# tuggerTrackerV1.net
KiCad netlist of a schematic drawn in EAGLE
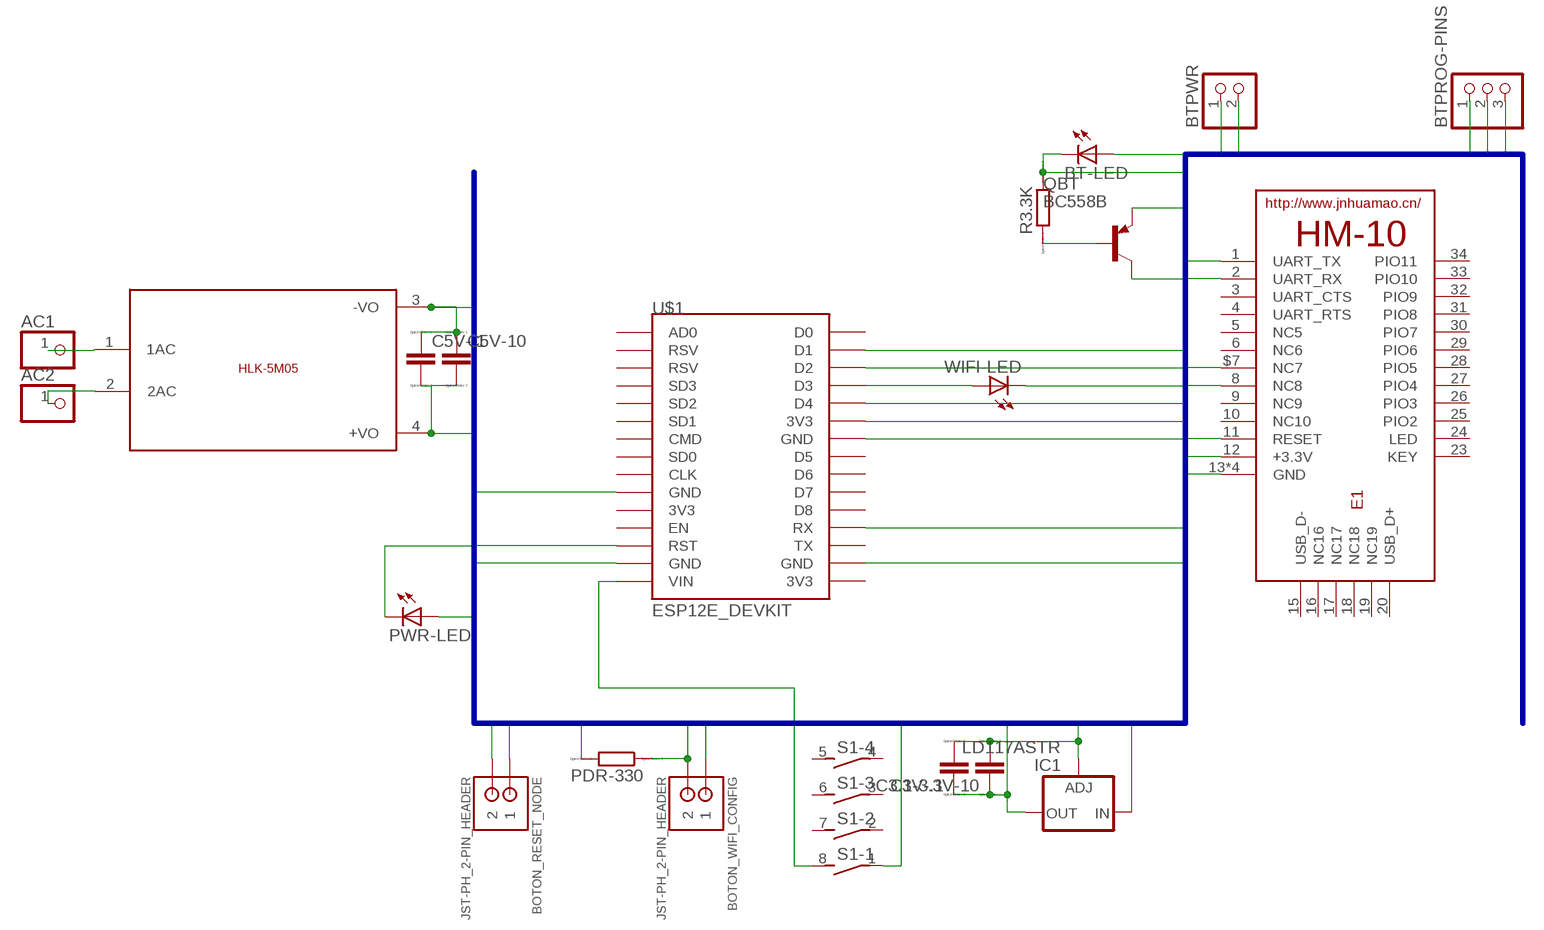
[diagram p0: schematic, sheet 1]

(export (version "E")
  (design (tool "Eeschema 10.0.6"))
  (components
    (comp (ref "AC1")
      (value "PINHD-1X1")
      (footprint "eagle-import:1X01")
      (libsource (lib "eagle-import") (part "PINHD-1X1"))
    )
    (comp (ref "AC2")
      (value "PINHD-1X1")
      (footprint "eagle-import:1X01")
      (libsource (lib "eagle-import") (part "PINHD-1X1"))
    )
    (comp (ref "BOTON_RESET_NODE")
      (value "JST-PH_2-PIN_HEADER")
      (footprint "eagle-import:JST_B2B-PH_HEADER")
      (libsource (lib "eagle-import") (part "JST-PH_2-PIN_HEADER"))
    )
    (comp (ref "BOTON_WIFI_CONFIG")
      (value "JST-PH_2-PIN_HEADER")
      (footprint "eagle-import:JST_B2B-PH_HEADER")
      (libsource (lib "eagle-import") (part "JST-PH_2-PIN_HEADER"))
    )
    (comp (ref "BT-LED")
      (value "LEDCHIPLED_1206")
      (footprint "eagle-import:CHIPLED_1206")
      (libsource (lib "eagle-import") (part "LEDCHIPLED_1206"))
    )
    (comp (ref "BTPROG-PINS")
      (value "PINHD-1X3")
      (footprint "eagle-import:1X03")
      (libsource (lib "eagle-import") (part "PINHD-1X3"))
    )
    (comp (ref "BTPWR")
      (value "PINHD-1X2")
      (footprint "eagle-import:1X02")
      (libsource (lib "eagle-import") (part "PINHD-1X2"))
    )
    (comp (ref "C1-3.3V-10")
      (value "CC0603")
      (footprint "eagle-import:C0603")
      (libsource (lib "eagle-import") (part "CC0603"))
    )
    (comp (ref "C3.3V-.1")
      (value "CC0603")
      (footprint "eagle-import:C0603")
      (libsource (lib "eagle-import") (part "CC0603"))
    )
    (comp (ref "C5V-.1")
      (value "CC0603")
      (footprint "eagle-import:C0603")
      (libsource (lib "eagle-import") (part "CC0603"))
    )
    (comp (ref "C5V-10")
      (value "CC0603")
      (footprint "eagle-import:C0603")
      (libsource (lib "eagle-import") (part "CC0603"))
    )
    (comp (ref "E1")
      (value "HM-10-BOARD")
      (footprint "eagle-import:26.9X13X2.2_BOARD")
      (libsource (lib "eagle-import") (part "HM-10-BOARD"))
    )
    (comp (ref "IC1")
      (value "LD117ASTR")
      (footprint "eagle-import:SOT223")
      (libsource (lib "eagle-import") (part "LD117A?STR"))
    )
    (comp (ref "PDR-330")
      (value "RR1206")
      (footprint "eagle-import:R1206")
      (libsource (lib "eagle-import") (part "RR1206"))
    )
    (comp (ref "PWR-LED")
      (value "LEDCHIPLED_1206")
      (footprint "eagle-import:CHIPLED_1206")
      (libsource (lib "eagle-import") (part "LEDCHIPLED_1206"))
    )
    (comp (ref "QBT")
      (value "BC558B")
      (footprint "eagle-import:TO92-EBC")
      (libsource (lib "eagle-import") (part "BC558B"))
    )
    (comp (ref "R3.3K")
      (value "RR1206")
      (footprint "eagle-import:R1206")
      (libsource (lib "eagle-import") (part "RR1206"))
    )
    (comp (ref "S1")
      (value "DIP04S")
      (footprint "eagle-import:DIP04S")
      (libsource (lib "eagle-import") (part "DIP04S"))
    )
    (comp (ref "U$1")
      (value "ESP12E_DEVKIT")
      (footprint "eagle-import:ESP12E_DEVKIT")
      (libsource (lib "eagle-import") (part "ESP12E_DEVKIT"))
    )
    (comp (ref "U$2")
      (value "5VDC/5W")
      (footprint "eagle-import:HLK-5M05")
      (libsource (lib "eagle-import") (part "HLK-5M05"))
    )
    (comp (ref "WIFI-LED")
      (value "LEDCHIPLED_1206")
      (footprint "eagle-import:CHIPLED_1206")
      (libsource (lib "eagle-import") (part "LEDCHIPLED_1206"))
    )
  )
  (nets
    (net (code "1") (name "/BTPG1") (class "Default")
      (node (ref "BTPROG-PINS") (pin "1") (pinfunction "1_1") (pintype "passive"))
      (node (ref "E1") (pin "$7") (pinfunction "NC7_$7") (pintype "bidirectional"))
    )
    (net (code "2") (name "/BTPG2") (class "Default")
      (node (ref "BTPROG-PINS") (pin "2") (pinfunction "2_2") (pintype "passive"))
      (node (ref "E1") (pin "8") (pinfunction "NC8_8") (pintype "bidirectional"))
    )
    (net (code "3") (name "/BTRST") (class "Default")
      (node (ref "BTPROG-PINS") (pin "3") (pinfunction "3_3") (pintype "passive"))
      (node (ref "E1") (pin "11") (pinfunction "RESET_11") (pintype "bidirectional"))
    )
    (net (code "4") (name "/BTVCC") (class "Default")
      (node (ref "E1") (pin "12") (pinfunction "+3.3V_12") (pintype "bidirectional"))
      (node (ref "QBT") (pin "C") (pinfunction "C_C") (pintype "passive"))
    )
    (net (code "5") (name "/D1") (class "Default")
      (node (ref "BT-LED") (pin "C") (pinfunction "C_C") (pintype "passive"))
      (node (ref "R3.3K") (pin "2") (pinfunction "2_2") (pintype "passive"))
      (node (ref "U$1") (pin "D1") (pinfunction "D1_D1") (pintype "bidirectional"))
    )
    (net (code "6") (name "/D2") (class "Default")
      (node (ref "BOTON_WIFI_CONFIG") (pin "P2") (pinfunction "2_P2") (pintype "bidirectional"))
      (node (ref "PDR-330") (pin "1") (pinfunction "1_1") (pintype "passive"))
      (node (ref "U$1") (pin "D2") (pinfunction "D2_D2") (pintype "bidirectional"))
    )
    (net (code "7") (name "/GND") (class "Default")
      (node (ref "BOTON_RESET_NODE") (pin "P2") (pinfunction "2_P2") (pintype "bidirectional"))
      (node (ref "BTPWR") (pin "1") (pinfunction "1_1") (pintype "passive"))
      (node (ref "C1-3.3V-10") (pin "2") (pinfunction "2_2") (pintype "passive"))
      (node (ref "C3.3V-.1") (pin "2") (pinfunction "2_2") (pintype "passive"))
      (node (ref "C5V-.1") (pin "1") (pinfunction "1_1") (pintype "passive"))
      (node (ref "C5V-10") (pin "1") (pinfunction "1_1") (pintype "passive"))
      (node (ref "E1") (pin "13") (pinfunction "GND_13") (pintype "bidirectional"))
      (node (ref "E1") (pin "14") (pinfunction "GND_14") (pintype "bidirectional"))
      (node (ref "E1") (pin "21") (pinfunction "GND_21") (pintype "bidirectional"))
      (node (ref "E1") (pin "22") (pinfunction "GND_22") (pintype "bidirectional"))
      (node (ref "IC1") (pin "1") (pinfunction "ADJ_1") (pintype "input"))
      (node (ref "PDR-330") (pin "2") (pinfunction "2_2") (pintype "passive"))
      (node (ref "PWR-LED") (pin "C") (pinfunction "C_C") (pintype "passive"))
      (node (ref "U$1") (pin "GND@0") (pinfunction "GND_GND@0") (pintype "bidirectional"))
      (node (ref "U$1") (pin "GND@1") (pinfunction "GND_GND@1") (pintype "bidirectional"))
      (node (ref "U$1") (pin "GND@2") (pinfunction "GND_GND@2") (pintype "bidirectional"))
      (node (ref "U$1") (pin "GND@3") (pinfunction "GND_GND@3") (pintype "bidirectional"))
      (node (ref "U$2") (pin "3") (pinfunction "-VO_3") (pintype "bidirectional"))
      (node (ref "WIFI-LED") (pin "C") (pinfunction "C_C") (pintype "passive"))
    )
    (net (code "8") (name "/NODRST") (class "Default")
      (node (ref "BOTON_RESET_NODE") (pin "P1") (pinfunction "1_P1") (pintype "bidirectional"))
      (node (ref "U$1") (pin "RST") (pinfunction "RST_RST") (pintype "bidirectional"))
    )
    (net (code "9") (name "/NRXBTX") (class "Default")
      (node (ref "E1") (pin "1") (pinfunction "UART_TX_1") (pintype "bidirectional"))
      (node (ref "U$1") (pin "RX") (pinfunction "RX_RX") (pintype "bidirectional"))
    )
    (net (code "10") (name "/NTXBRX") (class "Default")
      (node (ref "E1") (pin "2") (pinfunction "UART_RX_2") (pintype "bidirectional"))
      (node (ref "U$1") (pin "D4") (pinfunction "D4_D4") (pintype "bidirectional"))
    )
    (net (code "11") (name "/V3NODE") (class "Default")
      (node (ref "BOTON_WIFI_CONFIG") (pin "P1") (pinfunction "1_P1") (pintype "bidirectional"))
      (node (ref "BT-LED") (pin "A") (pinfunction "A_A") (pintype "passive"))
      (node (ref "PWR-LED") (pin "A") (pinfunction "A_A") (pintype "passive"))
      (node (ref "U$1") (pin "3V3@1") (pinfunction "3V3_3V3@1") (pintype "bidirectional"))
    )
    (net (code "12") (name "/V3REG") (class "Default")
      (node (ref "C1-3.3V-10") (pin "1") (pinfunction "1_1") (pintype "passive"))
      (node (ref "C3.3V-.1") (pin "1") (pinfunction "1_1") (pintype "passive"))
      (node (ref "IC1") (pin "4") (pinfunction "OUT_4") (pintype "passive"))
      (node (ref "QBT") (pin "E") (pinfunction "E_E") (pintype "passive"))
    )
    (net (code "13") (name "/VIN") (class "Default")
      (node (ref "BTPWR") (pin "2") (pinfunction "2_2") (pintype "passive"))
      (node (ref "C5V-.1") (pin "2") (pinfunction "2_2") (pintype "passive"))
      (node (ref "C5V-10") (pin "2") (pinfunction "2_2") (pintype "passive"))
      (node (ref "IC1") (pin "3") (pinfunction "IN_3") (pintype "input"))
      (node (ref "S1") (pin "1") (pinfunction "1_1") (pintype "passive"))
      (node (ref "U$2") (pin "4") (pinfunction "+VO_4") (pintype "bidirectional"))
    )
    (net (code "14") (name "Net-(QBT-PadB)") (class "Default")
      (node (ref "QBT") (pin "B") (pinfunction "B_B") (pintype "passive"))
      (node (ref "R3.3K") (pin "1") (pinfunction "1_1") (pintype "passive"))
    )
    (net (code "15") (name "Net-(S1A-2)") (class "Default")
      (node (ref "S1") (pin "8") (pinfunction "2_8") (pintype "passive"))
      (node (ref "U$1") (pin "VIN") (pinfunction "VIN_VIN") (pintype "bidirectional"))
    )
    (net (code "16") (name "Net-(U$1-PadD3)") (class "Default")
      (node (ref "U$1") (pin "D3") (pinfunction "D3_D3") (pintype "bidirectional"))
      (node (ref "WIFI-LED") (pin "A") (pinfunction "A_A") (pintype "passive"))
    )
    (net (code "17") (name "Net-(U$2-1AC)") (class "Default")
      (node (ref "AC1") (pin "1") (pinfunction "1_1") (pintype "passive"))
      (node (ref "U$2") (pin "1") (pinfunction "1AC_1") (pintype "bidirectional"))
    )
    (net (code "18") (name "Net-(U$2-2AC)") (class "Default")
      (node (ref "AC2") (pin "1") (pinfunction "1_1") (pintype "passive"))
      (node (ref "U$2") (pin "2") (pinfunction "2AC_2") (pintype "bidirectional"))
    )
    (net (code "19") (name "unconnected-(E1-KEY-Pad23)") (class "Default")
      (node (ref "E1") (pin "23") (pinfunction "KEY_23") (pintype "bidirectional"))
    )
    (net (code "20") (name "unconnected-(E1-LED-Pad24)") (class "Default")
      (node (ref "E1") (pin "24") (pinfunction "LED_24") (pintype "bidirectional"))
    )
    (net (code "21") (name "unconnected-(E1-NC5-Pad5)") (class "Default")
      (node (ref "E1") (pin "5") (pinfunction "NC5_5") (pintype "bidirectional"))
    )
    (net (code "22") (name "unconnected-(E1-NC6-Pad6)") (class "Default")
      (node (ref "E1") (pin "6") (pinfunction "NC6_6") (pintype "bidirectional"))
    )
    (net (code "23") (name "unconnected-(E1-NC9-Pad9)") (class "Default")
      (node (ref "E1") (pin "9") (pinfunction "NC9_9") (pintype "bidirectional"))
    )
    (net (code "24") (name "unconnected-(E1-NC10-Pad10)") (class "Default")
      (node (ref "E1") (pin "10") (pinfunction "NC10_10") (pintype "bidirectional"))
    )
    (net (code "25") (name "unconnected-(E1-NC16-Pad16)") (class "Default")
      (node (ref "E1") (pin "16") (pinfunction "NC16_16") (pintype "bidirectional"))
    )
    (net (code "26") (name "unconnected-(E1-NC17-Pad17)") (class "Default")
      (node (ref "E1") (pin "17") (pinfunction "NC17_17") (pintype "bidirectional"))
    )
    (net (code "27") (name "unconnected-(E1-NC18-Pad18)") (class "Default")
      (node (ref "E1") (pin "18") (pinfunction "NC18_18") (pintype "bidirectional"))
    )
    (net (code "28") (name "unconnected-(E1-NC19-Pad19)") (class "Default")
      (node (ref "E1") (pin "19") (pinfunction "NC19_19") (pintype "bidirectional"))
    )
    (net (code "29") (name "unconnected-(E1-PIO2-Pad25)") (class "Default")
      (node (ref "E1") (pin "25") (pinfunction "PIO2_25") (pintype "bidirectional"))
    )
    (net (code "30") (name "unconnected-(E1-PIO3-Pad26)") (class "Default")
      (node (ref "E1") (pin "26") (pinfunction "PIO3_26") (pintype "bidirectional"))
    )
    (net (code "31") (name "unconnected-(E1-PIO4-Pad27)") (class "Default")
      (node (ref "E1") (pin "27") (pinfunction "PIO4_27") (pintype "bidirectional"))
    )
    (net (code "32") (name "unconnected-(E1-PIO5-Pad28)") (class "Default")
      (node (ref "E1") (pin "28") (pinfunction "PIO5_28") (pintype "bidirectional"))
    )
    (net (code "33") (name "unconnected-(E1-PIO6-Pad29)") (class "Default")
      (node (ref "E1") (pin "29") (pinfunction "PIO6_29") (pintype "bidirectional"))
    )
    (net (code "34") (name "unconnected-(E1-PIO7-Pad30)") (class "Default")
      (node (ref "E1") (pin "30") (pinfunction "PIO7_30") (pintype "bidirectional"))
    )
    (net (code "35") (name "unconnected-(E1-PIO8-Pad31)") (class "Default")
      (node (ref "E1") (pin "31") (pinfunction "PIO8_31") (pintype "bidirectional"))
    )
    (net (code "36") (name "unconnected-(E1-PIO9-Pad32)") (class "Default")
      (node (ref "E1") (pin "32") (pinfunction "PIO9_32") (pintype "bidirectional"))
    )
    (net (code "37") (name "unconnected-(E1-PIO10-Pad33)") (class "Default")
      (node (ref "E1") (pin "33") (pinfunction "PIO10_33") (pintype "bidirectional"))
    )
    (net (code "38") (name "unconnected-(E1-PIO11-Pad34)") (class "Default")
      (node (ref "E1") (pin "34") (pinfunction "PIO11_34") (pintype "bidirectional"))
    )
    (net (code "39") (name "unconnected-(E1-UART_CTS-Pad3)") (class "Default")
      (node (ref "E1") (pin "3") (pinfunction "UART_CTS_3") (pintype "bidirectional"))
    )
    (net (code "40") (name "unconnected-(E1-UART_RTS-Pad4)") (class "Default")
      (node (ref "E1") (pin "4") (pinfunction "UART_RTS_4") (pintype "bidirectional"))
    )
    (net (code "41") (name "unconnected-(E1-USB_D+-Pad20)") (class "Default")
      (node (ref "E1") (pin "20") (pinfunction "USB_D+_20") (pintype "bidirectional"))
    )
    (net (code "42") (name "unconnected-(E1-USB_D--Pad15)") (class "Default")
      (node (ref "E1") (pin "15") (pinfunction "USB_D-_15") (pintype "bidirectional"))
    )
    (net (code "43") (name "unconnected-(S1B-1-Pad2)") (class "Default")
      (node (ref "S1") (pin "2") (pinfunction "1_2") (pintype "passive"))
    )
    (net (code "44") (name "unconnected-(S1B-2-Pad7)") (class "Default")
      (node (ref "S1") (pin "7") (pinfunction "2_7") (pintype "passive"))
    )
    (net (code "45") (name "unconnected-(S1C-1-Pad3)") (class "Default")
      (node (ref "S1") (pin "3") (pinfunction "1_3") (pintype "passive"))
    )
    (net (code "46") (name "unconnected-(S1C-2-Pad6)") (class "Default")
      (node (ref "S1") (pin "6") (pinfunction "2_6") (pintype "passive"))
    )
    (net (code "47") (name "unconnected-(S1D-1-Pad4)") (class "Default")
      (node (ref "S1") (pin "4") (pinfunction "1_4") (pintype "passive"))
    )
    (net (code "48") (name "unconnected-(S1D-2-Pad5)") (class "Default")
      (node (ref "S1") (pin "5") (pinfunction "2_5") (pintype "passive"))
    )
    (net (code "49") (name "unconnected-(U$1-3V3-Pad3V3@0)") (class "Default")
      (node (ref "U$1") (pin "3V3@0") (pinfunction "3V3_3V3@0") (pintype "bidirectional"))
    )
    (net (code "50") (name "unconnected-(U$1-3V3-Pad3V3@2)") (class "Default")
      (node (ref "U$1") (pin "3V3@2") (pinfunction "3V3_3V3@2") (pintype "bidirectional"))
    )
    (net (code "51") (name "unconnected-(U$1-PadAD0)") (class "Default")
      (node (ref "U$1") (pin "AD0") (pinfunction "AD0_AD0") (pintype "bidirectional"))
    )
    (net (code "52") (name "unconnected-(U$1-PadCLK)") (class "Default")
      (node (ref "U$1") (pin "CLK") (pinfunction "CLK_CLK") (pintype "bidirectional"))
    )
    (net (code "53") (name "unconnected-(U$1-PadCMD)") (class "Default")
      (node (ref "U$1") (pin "CMD") (pinfunction "CMD_CMD") (pintype "bidirectional"))
    )
    (net (code "54") (name "unconnected-(U$1-PadD0)") (class "Default")
      (node (ref "U$1") (pin "D0") (pinfunction "D0_D0") (pintype "bidirectional"))
    )
    (net (code "55") (name "unconnected-(U$1-PadD5)") (class "Default")
      (node (ref "U$1") (pin "D5") (pinfunction "D5_D5") (pintype "bidirectional"))
    )
    (net (code "56") (name "unconnected-(U$1-PadD6)") (class "Default")
      (node (ref "U$1") (pin "D6") (pinfunction "D6_D6") (pintype "bidirectional"))
    )
    (net (code "57") (name "unconnected-(U$1-PadD7)") (class "Default")
      (node (ref "U$1") (pin "D7") (pinfunction "D7_D7") (pintype "bidirectional"))
    )
    (net (code "58") (name "unconnected-(U$1-PadD8)") (class "Default")
      (node (ref "U$1") (pin "D8") (pinfunction "D8_D8") (pintype "bidirectional"))
    )
    (net (code "59") (name "unconnected-(U$1-PadEN)") (class "Default")
      (node (ref "U$1") (pin "EN") (pinfunction "EN_EN") (pintype "bidirectional"))
    )
    (net (code "60") (name "unconnected-(U$1-PadSD0)") (class "Default")
      (node (ref "U$1") (pin "SD0") (pinfunction "SD0_SD0") (pintype "bidirectional"))
    )
    (net (code "61") (name "unconnected-(U$1-PadSD1)") (class "Default")
      (node (ref "U$1") (pin "SD1") (pinfunction "SD1_SD1") (pintype "bidirectional"))
    )
    (net (code "62") (name "unconnected-(U$1-PadSD2)") (class "Default")
      (node (ref "U$1") (pin "SD2") (pinfunction "SD2_SD2") (pintype "bidirectional"))
    )
    (net (code "63") (name "unconnected-(U$1-PadSD3)") (class "Default")
      (node (ref "U$1") (pin "SD3") (pinfunction "SD3_SD3") (pintype "bidirectional"))
    )
    (net (code "64") (name "unconnected-(U$1-PadTX)") (class "Default")
      (node (ref "U$1") (pin "TX") (pinfunction "TX_TX") (pintype "bidirectional"))
    )
    (net (code "65") (name "unconnected-(U$1-RSV-PadRSV@0)") (class "Default")
      (node (ref "U$1") (pin "RSV@0") (pinfunction "RSV_RSV@0") (pintype "bidirectional"))
    )
    (net (code "66") (name "unconnected-(U$1-RSV-PadRSV@1)") (class "Default")
      (node (ref "U$1") (pin "RSV@1") (pinfunction "RSV_RSV@1") (pintype "bidirectional"))
    )
  )
)
